# 05-Connector.net
KiCad netlist of a schematic drawn in Altium Designer
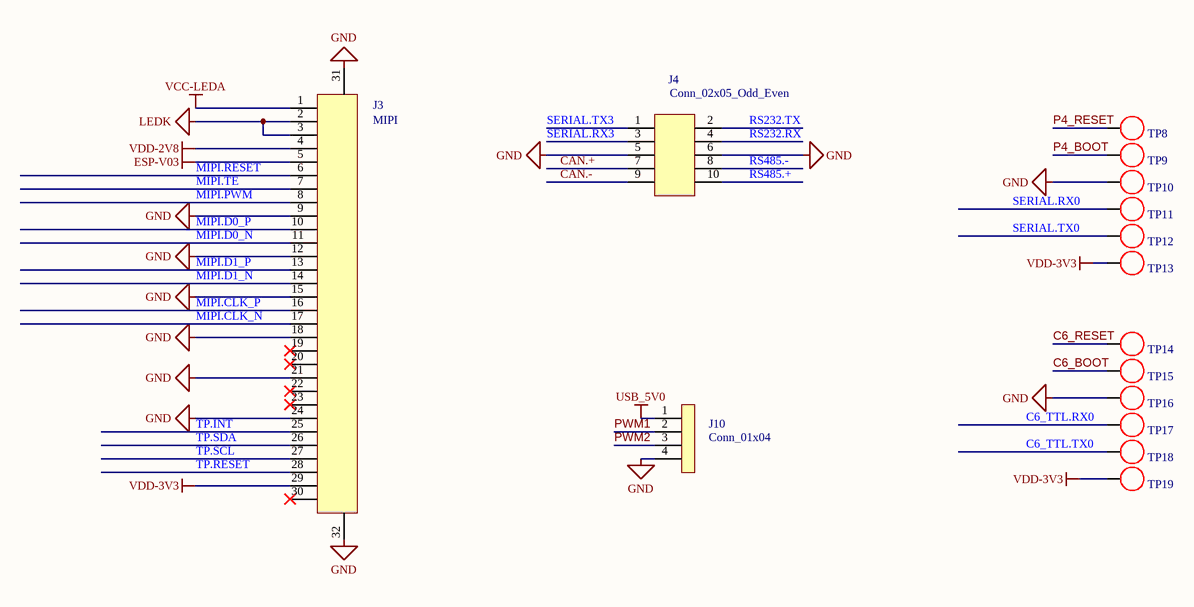
[diagram p0: 05-Connector.SchDoc]

(export (version "E")
  (design (tool "Eeschema 10.0.6"))
  (components
    (comp (ref "J3")
      (value "MIPI")
      (footprint "FPC-SMD_30P-P0.50_XUNPU_FPC-05F-30PH20")
      (libsource (lib "PCB_Project") (part "MIPI"))
    )
    (comp (ref "J4")
      (value "Conn_02x05_Odd_Even")
      (footprint "HDR-TH_10P-P2.54-H-M-R2-C5-S2.54-N")
      (libsource (lib "Schlib1") (part "Conn_02x05_Odd_Even"))
    )
    (comp (ref "J10")
      (value "Conn_01x04")
      (footprint "HDR-TH_4P-P2.54-H-M-W10.4")
      (libsource (lib "Schlib1") (part "Conn_01x04"))
    )
    (comp (ref "TP8") (value "TP8") (footprint "Test-Point-1*1mm") (libsource (lib "Schlib1") (part "TP?")))
    (comp (ref "TP9") (value "TP9") (footprint "Test-Point-1*1mm") (libsource (lib "Schlib1") (part "TP?")))
    (comp (ref "TP10") (value "TP10") (footprint "Test-Point-1*1mm") (libsource (lib "Schlib1") (part "TP?")))
    (comp (ref "TP11") (value "TP11") (footprint "Test-Point-1*1mm") (libsource (lib "Schlib1") (part "TP?")))
    (comp (ref "TP12") (value "TP12") (footprint "Test-Point-1*1mm") (libsource (lib "Schlib1") (part "TP?")))
    (comp (ref "TP13") (value "TP13") (footprint "Test-Point-1*1mm") (libsource (lib "Schlib1") (part "TP?")))
    (comp (ref "TP14") (value "TP14") (footprint "Test-Point-1*1mm") (libsource (lib "Schlib1") (part "TP?")))
    (comp (ref "TP15") (value "TP15") (footprint "Test-Point-1*1mm") (libsource (lib "Schlib1") (part "TP?")))
    (comp (ref "TP16") (value "TP16") (footprint "Test-Point-1*1mm") (libsource (lib "Schlib1") (part "TP?")))
    (comp (ref "TP17") (value "TP17") (footprint "Test-Point-1*1mm") (libsource (lib "Schlib1") (part "TP?")))
    (comp (ref "TP18") (value "TP18") (footprint "Test-Point-1*1mm") (libsource (lib "Schlib1") (part "TP?")))
    (comp (ref "TP19") (value "TP19") (footprint "Test-Point-1*1mm") (libsource (lib "Schlib1") (part "TP?")))
  )
  (nets
    (net (code "1") (name "/C6_BOOT") (class "Default")
      (node (ref "TP15") (pin "1") (pinfunction "1_1") (pintype "passive"))
    )
    (net (code "2") (name "/C6_RESET") (class "Default")
      (node (ref "TP14") (pin "1") (pinfunction "1_1") (pintype "passive"))
    )
    (net (code "3") (name "/C6_TTL.RX0") (class "Default")
      (node (ref "TP17") (pin "1") (pinfunction "1_1") (pintype "passive"))
    )
    (net (code "4") (name "/C6_TTL.TX0") (class "Default")
      (node (ref "TP18") (pin "1") (pinfunction "1_1") (pintype "passive"))
    )
    (net (code "5") (name "/CAN.+") (class "Default")
      (node (ref "J4") (pin "7") (pinfunction "7_7") (pintype "passive"))
    )
    (net (code "6") (name "/CAN.-") (class "Default")
      (node (ref "J4") (pin "9") (pinfunction "9_9") (pintype "passive"))
    )
    (net (code "7") (name "/MIPI.CLK_N") (class "Default")
      (node (ref "J3") (pin "17") (pinfunction "17_17") (pintype "passive"))
    )
    (net (code "8") (name "/MIPI.CLK_P") (class "Default")
      (node (ref "J3") (pin "16") (pinfunction "16_16") (pintype "passive"))
    )
    (net (code "9") (name "/MIPI.D0_N") (class "Default")
      (node (ref "J3") (pin "11") (pinfunction "11_11") (pintype "passive"))
    )
    (net (code "10") (name "/MIPI.D0_P") (class "Default")
      (node (ref "J3") (pin "10") (pinfunction "10_10") (pintype "passive"))
    )
    (net (code "11") (name "/MIPI.D1_N") (class "Default")
      (node (ref "J3") (pin "14") (pinfunction "14_14") (pintype "passive"))
    )
    (net (code "12") (name "/MIPI.D1_P") (class "Default")
      (node (ref "J3") (pin "13") (pinfunction "13_13") (pintype "passive"))
    )
    (net (code "13") (name "/MIPI.PWM") (class "Default")
      (node (ref "J3") (pin "8") (pinfunction "8_8") (pintype "passive"))
    )
    (net (code "14") (name "/MIPI.RESET") (class "Default")
      (node (ref "J3") (pin "6") (pinfunction "6_6") (pintype "passive"))
    )
    (net (code "15") (name "/MIPI.TE") (class "Default")
      (node (ref "J3") (pin "7") (pinfunction "7_7") (pintype "passive"))
    )
    (net (code "16") (name "/P4_BOOT") (class "Default")
      (node (ref "TP9") (pin "1") (pinfunction "1_1") (pintype "passive"))
    )
    (net (code "17") (name "/P4_RESET") (class "Default")
      (node (ref "TP8") (pin "1") (pinfunction "1_1") (pintype "passive"))
    )
    (net (code "18") (name "/PWM1") (class "Default")
      (node (ref "J10") (pin "2") (pinfunction "2_2") (pintype "passive"))
    )
    (net (code "19") (name "/PWM2") (class "Default")
      (node (ref "J10") (pin "3") (pinfunction "3_3") (pintype "passive"))
    )
    (net (code "20") (name "/RS232.RX") (class "Default")
      (node (ref "J4") (pin "4") (pinfunction "4_4") (pintype "passive"))
    )
    (net (code "21") (name "/RS232.TX") (class "Default")
      (node (ref "J4") (pin "2") (pinfunction "2_2") (pintype "passive"))
    )
    (net (code "22") (name "/RS485.+") (class "Default")
      (node (ref "J4") (pin "10") (pinfunction "10_10") (pintype "passive"))
    )
    (net (code "23") (name "/RS485.-") (class "Default")
      (node (ref "J4") (pin "8") (pinfunction "8_8") (pintype "passive"))
    )
    (net (code "24") (name "/SERIAL.RX0") (class "Default")
      (node (ref "TP11") (pin "1") (pinfunction "1_1") (pintype "passive"))
    )
    (net (code "25") (name "/SERIAL.RX3") (class "Default")
      (node (ref "J4") (pin "3") (pinfunction "3_3") (pintype "passive"))
    )
    (net (code "26") (name "/SERIAL.TX0") (class "Default")
      (node (ref "TP12") (pin "1") (pinfunction "1_1") (pintype "passive"))
    )
    (net (code "27") (name "/SERIAL.TX3") (class "Default")
      (node (ref "J4") (pin "1") (pinfunction "1_1") (pintype "passive"))
    )
    (net (code "28") (name "/TP.INT") (class "Default")
      (node (ref "J3") (pin "25") (pinfunction "25_25") (pintype "passive"))
    )
    (net (code "29") (name "/TP.RESET") (class "Default")
      (node (ref "J3") (pin "28") (pinfunction "28_28") (pintype "passive"))
    )
    (net (code "30") (name "/TP.SCL") (class "Default")
      (node (ref "J3") (pin "27") (pinfunction "27_27") (pintype "passive"))
    )
    (net (code "31") (name "/TP.SDA") (class "Default")
      (node (ref "J3") (pin "26") (pinfunction "26_26") (pintype "passive"))
    )
    (net (code "32") (name "ESP-V03") (class "Default")
      (node (ref "J3") (pin "5") (pinfunction "5_5") (pintype "passive"))
    )
    (net (code "33") (name "GND") (class "Default")
      (node (ref "J10") (pin "4") (pinfunction "4_4") (pintype "passive"))
      (node (ref "J3") (pin "12") (pinfunction "12_12") (pintype "passive"))
      (node (ref "J3") (pin "15") (pinfunction "15_15") (pintype "passive"))
      (node (ref "J3") (pin "18") (pinfunction "18_18") (pintype "passive"))
      (node (ref "J3") (pin "21") (pinfunction "21_21") (pintype "passive"))
      (node (ref "J3") (pin "24") (pinfunction "24_24") (pintype "passive"))
      (node (ref "J3") (pin "31") (pinfunction "31_31") (pintype "passive"))
      (node (ref "J3") (pin "32") (pinfunction "32_32") (pintype "passive"))
      (node (ref "J3") (pin "9") (pinfunction "9_9") (pintype "passive"))
      (node (ref "J4") (pin "5") (pinfunction "5_5") (pintype "passive"))
      (node (ref "J4") (pin "6") (pinfunction "6_6") (pintype "passive"))
      (node (ref "TP10") (pin "1") (pinfunction "1_1") (pintype "passive"))
      (node (ref "TP16") (pin "1") (pinfunction "1_1") (pintype "passive"))
    )
    (net (code "34") (name "LEDK") (class "Default")
      (node (ref "J3") (pin "2") (pinfunction "2_2") (pintype "passive"))
      (node (ref "J3") (pin "3") (pinfunction "3_3") (pintype "passive"))
    )
    (net (code "35") (name "USB_5V0") (class "Default")
      (node (ref "J10") (pin "1") (pinfunction "1_1") (pintype "passive"))
    )
    (net (code "36") (name "VCC-LEDA") (class "Default")
      (node (ref "J3") (pin "1") (pinfunction "1_1") (pintype "passive"))
    )
    (net (code "37") (name "VDD-2V8") (class "Default")
      (node (ref "J3") (pin "4") (pinfunction "4_4") (pintype "passive"))
    )
    (net (code "38") (name "VDD-3V3") (class "Default")
      (node (ref "J3") (pin "29") (pinfunction "29_29") (pintype "passive"))
      (node (ref "TP13") (pin "1") (pinfunction "1_1") (pintype "passive"))
      (node (ref "TP19") (pin "1") (pinfunction "1_1") (pintype "passive"))
    )
    (net (code "39") (name "unconnected-(J3-Pad19)") (class "Default")
      (node (ref "J3") (pin "19") (pinfunction "19_19") (pintype "passive+no_connect"))
    )
    (net (code "40") (name "unconnected-(J3-Pad20)") (class "Default")
      (node (ref "J3") (pin "20") (pinfunction "20_20") (pintype "passive+no_connect"))
    )
    (net (code "41") (name "unconnected-(J3-Pad22)") (class "Default")
      (node (ref "J3") (pin "22") (pinfunction "22_22") (pintype "passive+no_connect"))
    )
    (net (code "42") (name "unconnected-(J3-Pad23)") (class "Default")
      (node (ref "J3") (pin "23") (pinfunction "23_23") (pintype "passive+no_connect"))
    )
    (net (code "43") (name "unconnected-(J3-Pad30)") (class "Default")
      (node (ref "J3") (pin "30") (pinfunction "30_30") (pintype "passive+no_connect"))
    )
  )
)
